# samd51breakout.net
KiCad netlist of a schematic drawn in EAGLE
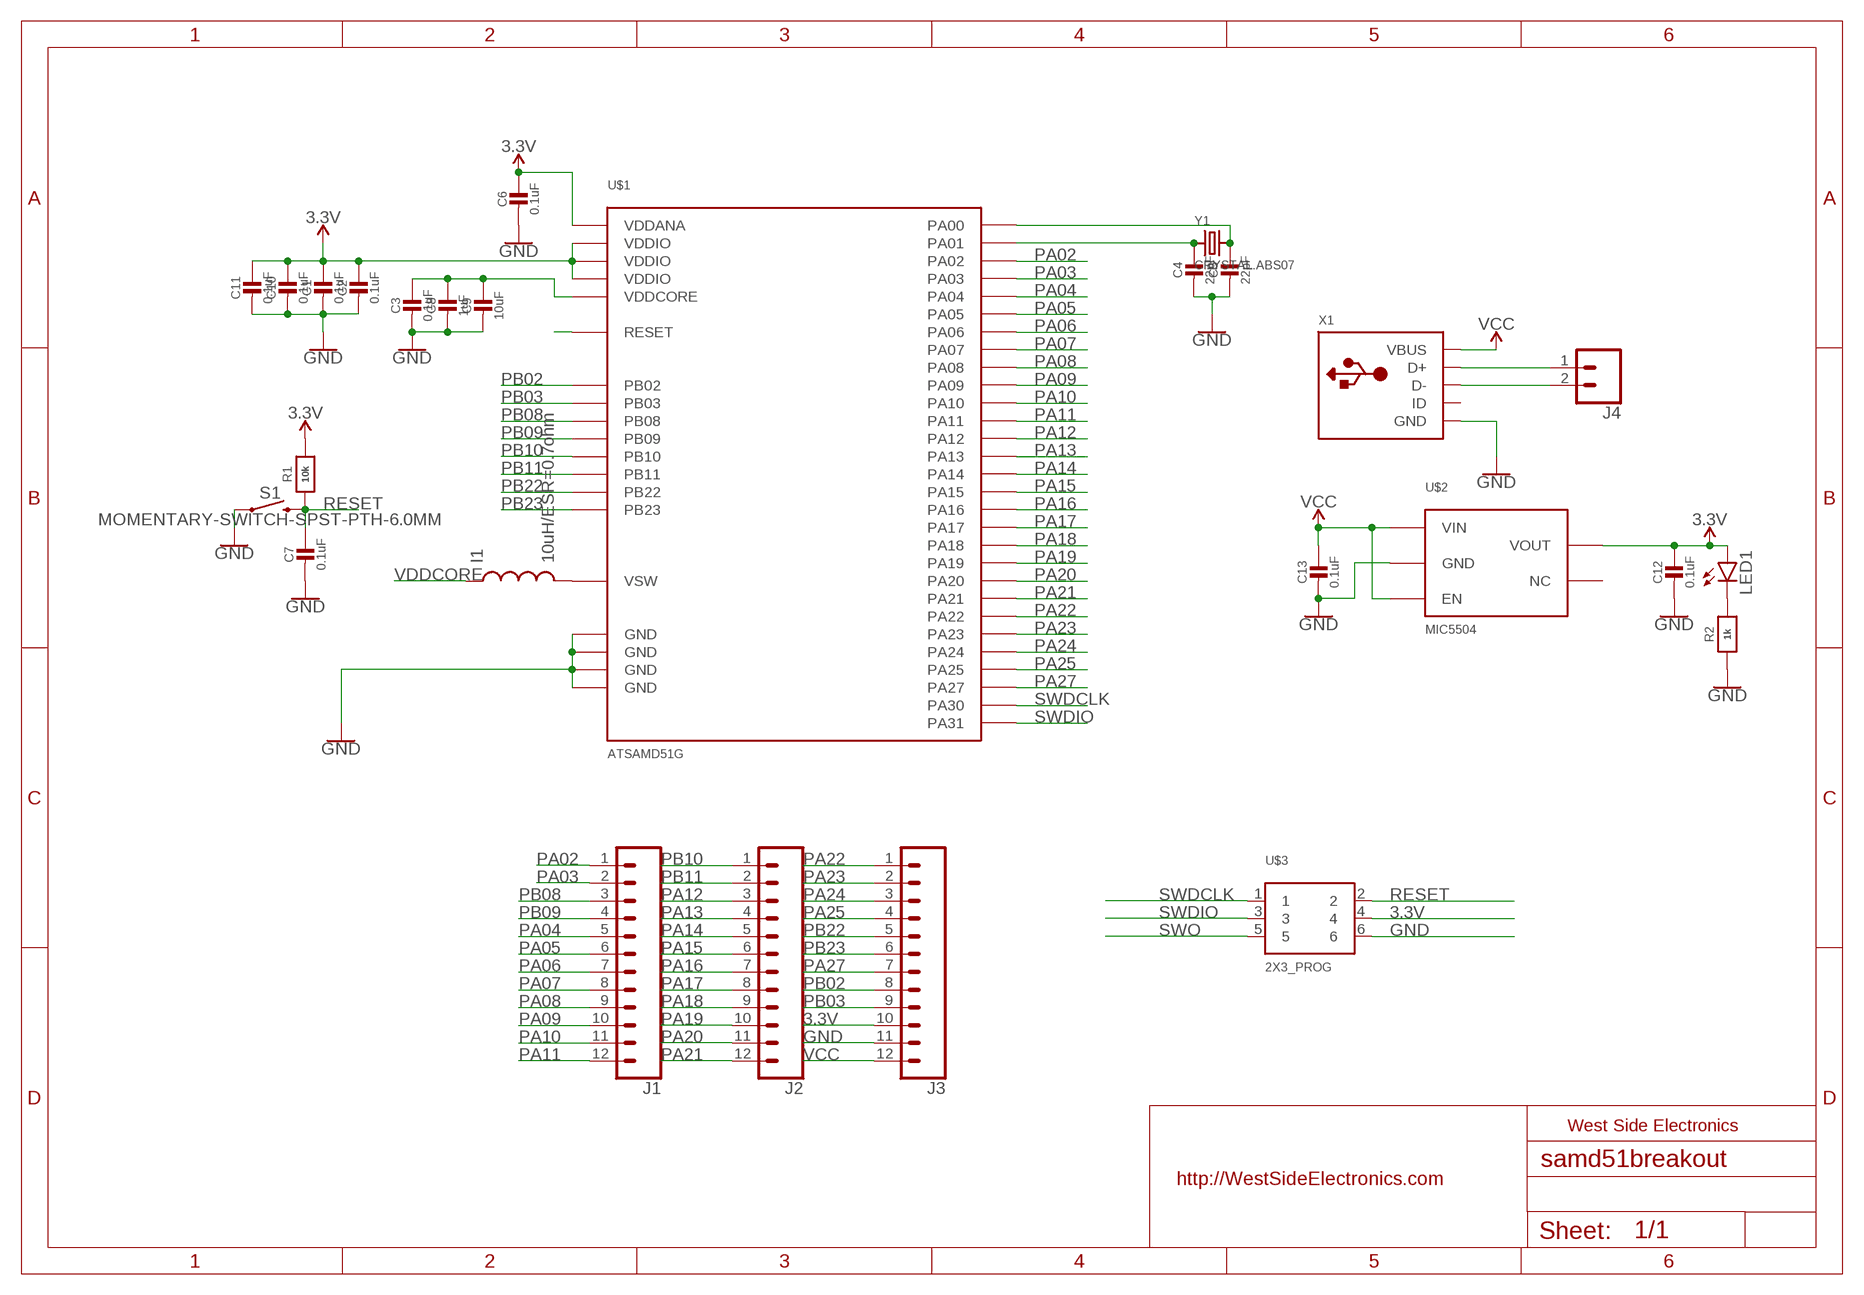
[diagram p0: schematic, sheet 1]

(export (version "E")
  (design (tool "Eeschema 10.0.6"))
  (components
    (comp (ref "C1")
      (value "0.1uF")
      (footprint "eagle-import:_0603MP")
      (libsource (lib "eagle-import") (part "CAP_CERAMIC_0603MP"))
    )
    (comp (ref "C2")
      (value "0.1uF")
      (footprint "eagle-import:_0603MP")
      (libsource (lib "eagle-import") (part "CAP_CERAMIC_0603MP"))
    )
    (comp (ref "C3")
      (value "0.1uF")
      (footprint "eagle-import:_0603MP")
      (libsource (lib "eagle-import") (part "CAP_CERAMIC_0603MP"))
    )
    (comp (ref "C4")
      (value "22pF")
      (footprint "eagle-import:_0603MP")
      (libsource (lib "eagle-import") (part "CAP_CERAMIC_0603MP"))
    )
    (comp (ref "C5")
      (value "22pF")
      (footprint "eagle-import:_0603MP")
      (libsource (lib "eagle-import") (part "CAP_CERAMIC_0603MP"))
    )
    (comp (ref "C6")
      (value "0.1uF")
      (footprint "eagle-import:_0603MP")
      (libsource (lib "eagle-import") (part "CAP_CERAMIC_0603MP"))
    )
    (comp (ref "C7")
      (value "0.1uF")
      (footprint "eagle-import:_0603MP")
      (libsource (lib "eagle-import") (part "CAP_CERAMIC_0603MP"))
    )
    (comp (ref "C8")
      (value "1uF")
      (footprint "eagle-import:_0603MP")
      (libsource (lib "eagle-import") (part "CAP_CERAMIC_0603MP"))
    )
    (comp (ref "C9")
      (value "10uF")
      (footprint "eagle-import:_0603MP")
      (libsource (lib "eagle-import") (part "CAP_CERAMIC_0603MP"))
    )
    (comp (ref "C10")
      (value "0.1uF")
      (footprint "eagle-import:_0603MP")
      (libsource (lib "eagle-import") (part "CAP_CERAMIC_0603MP"))
    )
    (comp (ref "C11")
      (value "0.1uF")
      (footprint "eagle-import:_0603MP")
      (libsource (lib "eagle-import") (part "CAP_CERAMIC_0603MP"))
    )
    (comp (ref "C12")
      (value "0.1uF")
      (footprint "eagle-import:_0603MP")
      (libsource (lib "eagle-import") (part "CAP_CERAMIC_0603MP"))
    )
    (comp (ref "C13")
      (value "0.1uF")
      (footprint "eagle-import:_0603MP")
      (libsource (lib "eagle-import") (part "CAP_CERAMIC_0603MP"))
    )
    (comp (ref "I1")
      (value "10uH/ESR=0.7ohm")
      (footprint "eagle-import:0805")
      (libsource (lib "eagle-import") (part "IND"))
    )
    (comp (ref "J1")
      (value "CONN_12")
      (footprint "eagle-import:1X12")
      (libsource (lib "eagle-import") (part "CONN_12"))
    )
    (comp (ref "J2")
      (value "CONN_12")
      (footprint "eagle-import:1X12")
      (libsource (lib "eagle-import") (part "CONN_12"))
    )
    (comp (ref "J3")
      (value "CONN_12")
      (footprint "eagle-import:1X12")
      (libsource (lib "eagle-import") (part "CONN_12"))
    )
    (comp (ref "J4")
      (value "CONN_02")
      (footprint "eagle-import:1X02")
      (libsource (lib "eagle-import") (part "CONN_02"))
    )
    (comp (ref "LED1")
      (value "LED0603")
      (footprint "eagle-import:LED-0603")
      (libsource (lib "eagle-import") (part "LED0603"))
    )
    (comp (ref "R1")
      (value "10k")
      (footprint "eagle-import:_0603MP")
      (libsource (lib "eagle-import") (part "RESISTOR_0603MP"))
    )
    (comp (ref "R2")
      (value "1k")
      (footprint "eagle-import:_0603MP")
      (libsource (lib "eagle-import") (part "RESISTOR_0603MP"))
    )
    (comp (ref "S1")
      (value "MOMENTARY-SWITCH-SPST-PTH-6.0MM")
      (footprint "eagle-import:TACTILE_SWITCH_PTH_6.0MM")
      (libsource (lib "eagle-import") (part "MOMENTARY-SWITCH-SPST-PTH-6.0MM"))
    )
    (comp (ref "U$1")
      (value "ATSAMD51G")
      (footprint "eagle-import:QFN-48")
      (libsource (lib "eagle-import") (part "ATSAMD51G"))
    )
    (comp (ref "U$2")
      (value "MIC5504")
      (footprint "eagle-import:SOT23-5")
      (libsource (lib "eagle-import") (part "MIC5504"))
    )
    (comp (ref "U$3")
      (value "2X3_PROG")
      (footprint "eagle-import:2X3-SMD_PROG")
      (libsource (lib "eagle-import") (part "2X3_PROG"))
    )
    (comp (ref "X1")
      (value "MICROBUILDER_USB_MICRO_20329_V2")
      (footprint "eagle-import:MICROBUILDER_4UCONN_20329_V2")
      (libsource (lib "eagle-import") (part "MICROBUILDER_USB_MICRO_20329_V2"))
    )
    (comp (ref "Y1")
      (value "CRYSTAL.ABS07")
      (footprint "eagle-import:ABS07")
      (libsource (lib "eagle-import") (part "CRYSTAL.ABS07"))
    )
  )
  (nets
    (net (code "1") (name "/PA02") (class "Default")
      (node (ref "J1") (pin "1") (pinfunction "1_1") (pintype "passive"))
      (node (ref "U$1") (pin "3") (pinfunction "PA02_3") (pintype "bidirectional"))
    )
    (net (code "2") (name "/PA03") (class "Default")
      (node (ref "J1") (pin "2") (pinfunction "2_2") (pintype "passive"))
      (node (ref "U$1") (pin "4") (pinfunction "PA03_4") (pintype "bidirectional"))
    )
    (net (code "3") (name "/PA04") (class "Default")
      (node (ref "J1") (pin "5") (pinfunction "5_5") (pintype "passive"))
      (node (ref "U$1") (pin "9") (pinfunction "PA04_9") (pintype "bidirectional"))
    )
    (net (code "4") (name "/PA05") (class "Default")
      (node (ref "J1") (pin "6") (pinfunction "6_6") (pintype "passive"))
      (node (ref "U$1") (pin "10") (pinfunction "PA05_10") (pintype "bidirectional"))
    )
    (net (code "5") (name "/PA06") (class "Default")
      (node (ref "J1") (pin "7") (pinfunction "7_7") (pintype "passive"))
      (node (ref "U$1") (pin "11") (pinfunction "PA06_11") (pintype "bidirectional"))
    )
    (net (code "6") (name "/PA07") (class "Default")
      (node (ref "J1") (pin "8") (pinfunction "8_8") (pintype "passive"))
      (node (ref "U$1") (pin "12") (pinfunction "PA07_12") (pintype "bidirectional"))
    )
    (net (code "7") (name "/PA08") (class "Default")
      (node (ref "J1") (pin "9") (pinfunction "9_9") (pintype "passive"))
      (node (ref "U$1") (pin "13") (pinfunction "PA08_13") (pintype "bidirectional"))
    )
    (net (code "8") (name "/PA09") (class "Default")
      (node (ref "J1") (pin "10") (pinfunction "10_10") (pintype "passive"))
      (node (ref "U$1") (pin "14") (pinfunction "PA09_14") (pintype "bidirectional"))
    )
    (net (code "9") (name "/PA10") (class "Default")
      (node (ref "J1") (pin "11") (pinfunction "11_11") (pintype "passive"))
      (node (ref "U$1") (pin "15") (pinfunction "PA10_15") (pintype "bidirectional"))
    )
    (net (code "10") (name "/PA11") (class "Default")
      (node (ref "J1") (pin "12") (pinfunction "12_12") (pintype "passive"))
      (node (ref "U$1") (pin "16") (pinfunction "PA11_16") (pintype "bidirectional"))
    )
    (net (code "11") (name "/PA12") (class "Default")
      (node (ref "J2") (pin "3") (pinfunction "3_3") (pintype "passive"))
      (node (ref "U$1") (pin "21") (pinfunction "PA12_21") (pintype "bidirectional"))
    )
    (net (code "12") (name "/PA13") (class "Default")
      (node (ref "J2") (pin "4") (pinfunction "4_4") (pintype "passive"))
      (node (ref "U$1") (pin "22") (pinfunction "PA13_22") (pintype "bidirectional"))
    )
    (net (code "13") (name "/PA14") (class "Default")
      (node (ref "J2") (pin "5") (pinfunction "5_5") (pintype "passive"))
      (node (ref "U$1") (pin "23") (pinfunction "PA14_23") (pintype "bidirectional"))
    )
    (net (code "14") (name "/PA15") (class "Default")
      (node (ref "J2") (pin "6") (pinfunction "6_6") (pintype "passive"))
      (node (ref "U$1") (pin "24") (pinfunction "PA15_24") (pintype "bidirectional"))
    )
    (net (code "15") (name "/PA16") (class "Default")
      (node (ref "J2") (pin "7") (pinfunction "7_7") (pintype "passive"))
      (node (ref "U$1") (pin "25") (pinfunction "PA16_25") (pintype "bidirectional"))
    )
    (net (code "16") (name "/PA17") (class "Default")
      (node (ref "J2") (pin "8") (pinfunction "8_8") (pintype "passive"))
      (node (ref "U$1") (pin "26") (pinfunction "PA17_26") (pintype "bidirectional"))
    )
    (net (code "17") (name "/PA18") (class "Default")
      (node (ref "J2") (pin "9") (pinfunction "9_9") (pintype "passive"))
      (node (ref "U$1") (pin "27") (pinfunction "PA18_27") (pintype "bidirectional"))
    )
    (net (code "18") (name "/PA19") (class "Default")
      (node (ref "J2") (pin "10") (pinfunction "10_10") (pintype "passive"))
      (node (ref "U$1") (pin "28") (pinfunction "PA19_28") (pintype "bidirectional"))
    )
    (net (code "19") (name "/PA20") (class "Default")
      (node (ref "J2") (pin "11") (pinfunction "11_11") (pintype "passive"))
      (node (ref "U$1") (pin "29") (pinfunction "PA20_29") (pintype "bidirectional"))
    )
    (net (code "20") (name "/PA21") (class "Default")
      (node (ref "J2") (pin "12") (pinfunction "12_12") (pintype "passive"))
      (node (ref "U$1") (pin "30") (pinfunction "PA21_30") (pintype "bidirectional"))
    )
    (net (code "21") (name "/PA22") (class "Default")
      (node (ref "J3") (pin "1") (pinfunction "1_1") (pintype "passive"))
      (node (ref "U$1") (pin "31") (pinfunction "PA22_31") (pintype "bidirectional"))
    )
    (net (code "22") (name "/PA23") (class "Default")
      (node (ref "J3") (pin "2") (pinfunction "2_2") (pintype "passive"))
      (node (ref "U$1") (pin "32") (pinfunction "PA23_32") (pintype "bidirectional"))
    )
    (net (code "23") (name "/PA24") (class "Default")
      (node (ref "J3") (pin "3") (pinfunction "3_3") (pintype "passive"))
      (node (ref "U$1") (pin "33") (pinfunction "PA24_33") (pintype "bidirectional"))
    )
    (net (code "24") (name "/PA25") (class "Default")
      (node (ref "J3") (pin "4") (pinfunction "4_4") (pintype "passive"))
      (node (ref "U$1") (pin "34") (pinfunction "PA25_34") (pintype "bidirectional"))
    )
    (net (code "25") (name "/PA27") (class "Default")
      (node (ref "J3") (pin "7") (pinfunction "7_7") (pintype "passive"))
      (node (ref "U$1") (pin "39") (pinfunction "PA27_39") (pintype "bidirectional"))
    )
    (net (code "26") (name "/PB02") (class "Default")
      (node (ref "J3") (pin "8") (pinfunction "8_8") (pintype "passive"))
      (node (ref "U$1") (pin "47") (pinfunction "PB02_47") (pintype "bidirectional"))
    )
    (net (code "27") (name "/PB03") (class "Default")
      (node (ref "J3") (pin "9") (pinfunction "9_9") (pintype "passive"))
      (node (ref "U$1") (pin "48") (pinfunction "PB03_48") (pintype "bidirectional"))
    )
    (net (code "28") (name "/PB08") (class "Default")
      (node (ref "J1") (pin "3") (pinfunction "3_3") (pintype "passive"))
      (node (ref "U$1") (pin "7") (pinfunction "PB08_7") (pintype "bidirectional"))
    )
    (net (code "29") (name "/PB09") (class "Default")
      (node (ref "J1") (pin "4") (pinfunction "4_4") (pintype "passive"))
      (node (ref "U$1") (pin "8") (pinfunction "PB09_8") (pintype "bidirectional"))
    )
    (net (code "30") (name "/PB10") (class "Default")
      (node (ref "J2") (pin "1") (pinfunction "1_1") (pintype "passive"))
      (node (ref "U$1") (pin "19") (pinfunction "PB10_19") (pintype "bidirectional"))
    )
    (net (code "31") (name "/PB11") (class "Default")
      (node (ref "J2") (pin "2") (pinfunction "2_2") (pintype "passive"))
      (node (ref "U$1") (pin "20") (pinfunction "PB11_20") (pintype "bidirectional"))
    )
    (net (code "32") (name "/PB22") (class "Default")
      (node (ref "J3") (pin "5") (pinfunction "5_5") (pintype "passive"))
      (node (ref "U$1") (pin "37") (pinfunction "PB22_37") (pintype "bidirectional"))
    )
    (net (code "33") (name "/PB23") (class "Default")
      (node (ref "J3") (pin "6") (pinfunction "6_6") (pintype "passive"))
      (node (ref "U$1") (pin "38") (pinfunction "PB23_38") (pintype "bidirectional"))
    )
    (net (code "34") (name "/RESET") (class "Default")
      (node (ref "C7") (pin "1") (pinfunction "1_1") (pintype "passive"))
      (node (ref "R1") (pin "1") (pinfunction "1_1") (pintype "passive"))
      (node (ref "S1") (pin "3") (pinfunction "2_3") (pintype "passive"))
      (node (ref "U$1") (pin "40") (pinfunction "RESET_40") (pintype "bidirectional"))
      (node (ref "U$3") (pin "2") (pinfunction "2_2") (pintype "bidirectional"))
    )
    (net (code "35") (name "/SWDCLK") (class "Default")
      (node (ref "U$1") (pin "45") (pinfunction "PA30_45") (pintype "bidirectional"))
      (node (ref "U$3") (pin "1") (pinfunction "1_1") (pintype "bidirectional"))
    )
    (net (code "36") (name "/SWDIO") (class "Default")
      (node (ref "U$1") (pin "46") (pinfunction "PA31_46") (pintype "bidirectional"))
      (node (ref "U$3") (pin "3") (pinfunction "3_3") (pintype "bidirectional"))
    )
    (net (code "37") (name "/SWO") (class "Default")
      (node (ref "U$3") (pin "5") (pinfunction "5_5") (pintype "bidirectional"))
    )
    (net (code "38") (name "/VDDCORE") (class "Default")
      (node (ref "C3") (pin "1") (pinfunction "1_1") (pintype "passive"))
      (node (ref "C8") (pin "1") (pinfunction "1_1") (pintype "passive"))
      (node (ref "C9") (pin "1") (pinfunction "1_1") (pintype "passive"))
      (node (ref "I1") (pin "1") (pinfunction "1_1") (pintype "passive"))
      (node (ref "U$1") (pin "41") (pinfunction "VDDCORE_41") (pintype "bidirectional"))
    )
    (net (code "39") (name "3.3V") (class "Default")
      (node (ref "C1") (pin "1") (pinfunction "1_1") (pintype "passive"))
      (node (ref "C10") (pin "1") (pinfunction "1_1") (pintype "passive"))
      (node (ref "C11") (pin "1") (pinfunction "1_1") (pintype "passive"))
      (node (ref "C12") (pin "1") (pinfunction "1_1") (pintype "passive"))
      (node (ref "C2") (pin "1") (pinfunction "1_1") (pintype "passive"))
      (node (ref "C6") (pin "1") (pinfunction "1_1") (pintype "passive"))
      (node (ref "J3") (pin "10") (pinfunction "10_10") (pintype "passive"))
      (node (ref "LED1") (pin "A") (pinfunction "A_A") (pintype "passive"))
      (node (ref "R1") (pin "2") (pinfunction "2_2") (pintype "passive"))
      (node (ref "U$1") (pin "17") (pinfunction "VDDIO_17") (pintype "bidirectional"))
      (node (ref "U$1") (pin "36") (pinfunction "VDDIO_36") (pintype "bidirectional"))
      (node (ref "U$1") (pin "44") (pinfunction "VDDIO_44") (pintype "bidirectional"))
      (node (ref "U$1") (pin "6") (pinfunction "VDDANA_6") (pintype "bidirectional"))
      (node (ref "U$2") (pin "5") (pinfunction "VOUT_5") (pintype "bidirectional"))
      (node (ref "U$3") (pin "4") (pinfunction "4_4") (pintype "bidirectional"))
    )
    (net (code "40") (name "GND") (class "Default")
      (node (ref "C1") (pin "2") (pinfunction "2_2") (pintype "passive"))
      (node (ref "C10") (pin "2") (pinfunction "2_2") (pintype "passive"))
      (node (ref "C11") (pin "2") (pinfunction "2_2") (pintype "passive"))
      (node (ref "C12") (pin "2") (pinfunction "2_2") (pintype "passive"))
      (node (ref "C13") (pin "2") (pinfunction "2_2") (pintype "passive"))
      (node (ref "C2") (pin "2") (pinfunction "2_2") (pintype "passive"))
      (node (ref "C3") (pin "2") (pinfunction "2_2") (pintype "passive"))
      (node (ref "C4") (pin "2") (pinfunction "2_2") (pintype "passive"))
      (node (ref "C5") (pin "2") (pinfunction "2_2") (pintype "passive"))
      (node (ref "C6") (pin "2") (pinfunction "2_2") (pintype "passive"))
      (node (ref "C7") (pin "2") (pinfunction "2_2") (pintype "passive"))
      (node (ref "C8") (pin "2") (pinfunction "2_2") (pintype "passive"))
      (node (ref "C9") (pin "2") (pinfunction "2_2") (pintype "passive"))
      (node (ref "J3") (pin "11") (pinfunction "11_11") (pintype "passive"))
      (node (ref "R2") (pin "1") (pinfunction "1_1") (pintype "passive"))
      (node (ref "S1") (pin "1") (pinfunction "1_1") (pintype "passive"))
      (node (ref "U$1") (pin "18") (pinfunction "GND_18") (pintype "bidirectional"))
      (node (ref "U$1") (pin "35") (pinfunction "GND_35") (pintype "bidirectional"))
      (node (ref "U$1") (pin "42") (pinfunction "GND_42") (pintype "bidirectional"))
      (node (ref "U$1") (pin "5") (pinfunction "GND_5") (pintype "bidirectional"))
      (node (ref "U$2") (pin "2") (pinfunction "GND_2") (pintype "bidirectional"))
      (node (ref "U$3") (pin "6") (pinfunction "6_6") (pintype "bidirectional"))
      (node (ref "X1") (pin "BASE@1") (pinfunction "GND_BASE@1") (pintype "power_in"))
      (node (ref "X1") (pin "BASE@2") (pinfunction "GND_BASE@2") (pintype "power_in"))
      (node (ref "X1") (pin "GND") (pinfunction "GND_GND") (pintype "power_in"))
      (node (ref "X1") (pin "SPRT@1") (pinfunction "GND_SPRT@1") (pintype "power_in"))
      (node (ref "X1") (pin "SPRT@2") (pinfunction "GND_SPRT@2") (pintype "power_in"))
      (node (ref "X1") (pin "SPRT@3") (pinfunction "GND_SPRT@3") (pintype "power_in"))
      (node (ref "X1") (pin "SPRT@4") (pinfunction "GND_SPRT@4") (pintype "power_in"))
    )
    (net (code "41") (name "Net-(J4-Pad1)") (class "Default")
      (node (ref "J4") (pin "1") (pinfunction "1_1") (pintype "passive"))
      (node (ref "X1") (pin "D+") (pinfunction "D+_D+") (pintype "bidirectional"))
    )
    (net (code "42") (name "Net-(J4-Pad2)") (class "Default")
      (node (ref "J4") (pin "2") (pinfunction "2_2") (pintype "passive"))
      (node (ref "X1") (pin "D-") (pinfunction "D-_D-") (pintype "bidirectional"))
    )
    (net (code "43") (name "Net-(LED1-PadC)") (class "Default")
      (node (ref "LED1") (pin "C") (pinfunction "C_C") (pintype "passive"))
      (node (ref "R2") (pin "2") (pinfunction "2_2") (pintype "passive"))
    )
    (net (code "44") (name "Net-(U$1-PA00)") (class "Default")
      (node (ref "C5") (pin "1") (pinfunction "1_1") (pintype "passive"))
      (node (ref "U$1") (pin "1") (pinfunction "PA00_1") (pintype "bidirectional"))
      (node (ref "Y1") (pin "2") (pinfunction "2_2") (pintype "passive"))
    )
    (net (code "45") (name "Net-(U$1-PA01)") (class "Default")
      (node (ref "C4") (pin "1") (pinfunction "1_1") (pintype "passive"))
      (node (ref "U$1") (pin "2") (pinfunction "PA01_2") (pintype "bidirectional"))
      (node (ref "Y1") (pin "1") (pinfunction "1_1") (pintype "passive"))
    )
    (net (code "46") (name "Net-(U$1-VSW)") (class "Default")
      (node (ref "I1") (pin "2") (pinfunction "2_2") (pintype "passive"))
      (node (ref "U$1") (pin "43") (pinfunction "VSW_43") (pintype "bidirectional"))
    )
    (net (code "47") (name "VCC") (class "Default")
      (node (ref "C13") (pin "1") (pinfunction "1_1") (pintype "passive"))
      (node (ref "J3") (pin "12") (pinfunction "12_12") (pintype "passive"))
      (node (ref "U$2") (pin "1") (pinfunction "VIN_1") (pintype "bidirectional"))
      (node (ref "U$2") (pin "3") (pinfunction "EN_3") (pintype "bidirectional"))
      (node (ref "X1") (pin "VBUS") (pinfunction "VBUS_VBUS") (pintype "power_in"))
    )
    (net (code "48") (name "unconnected-(U$2-NC-Pad4)") (class "Default")
      (node (ref "U$2") (pin "4") (pinfunction "NC_4") (pintype "bidirectional"))
    )
    (net (code "49") (name "unconnected-(X1-PadID)") (class "Default")
      (node (ref "X1") (pin "ID") (pinfunction "ID_ID") (pintype "bidirectional"))
    )
  )
)
